# PokerKidtestBoard.net
KiCad netlist of a schematic drawn in Altium Designer
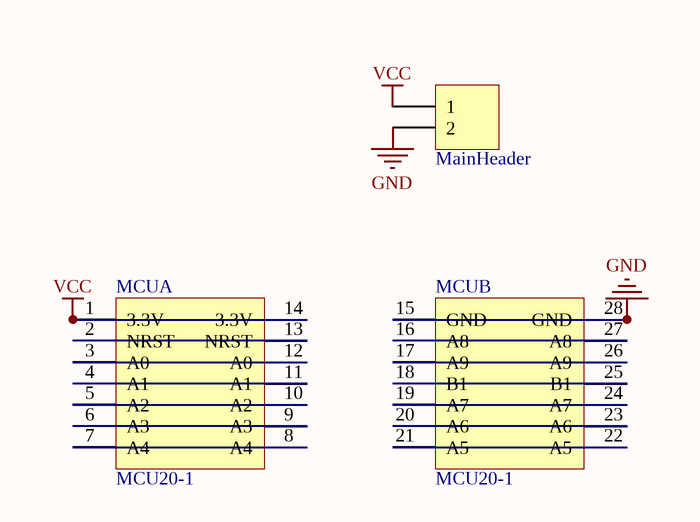
[diagram p0: PokerKidtestBoard.SchDoc]

(export (version "E")
  (design (tool "Eeschema 10.0.6"))
  (components
    (comp (ref "MainHeader")
      (value "691312510002")
      (footprint "691312510002")
      (description "WR-TBL Terminal Blocks Serie 312 – 5.08 mm")
      (fields
        (field (name "MANUFACTURER") "Würth Elektronik eiSos GmbH")
        (field (name "CREATED BY") "Karrer Zheng")
      )
      (libsource (lib "WE_WR-TBL_Pluggable System_5.08 mm_rev15basdasd") (part "691312510002"))
    )
    (comp (ref "MCU") (value "MCU20-1") (footprint "MCU20-1") (libsource (lib "Aryalib") (part "MCU20-1")))
  )
  (nets
    (net (code "1") (name "GND") (class "Default")
      (node (ref "MCU") (pin "15") (pinfunction "GND_15") (pintype "passive"))
      (node (ref "MCU") (pin "28") (pinfunction "GND_28") (pintype "passive"))
      (node (ref "MainHeader") (pin "2") (pinfunction "2_2") (pintype "passive"))
    )
    (net (code "2") (name "Net-(MCUA-A0-Pad12)") (class "Default")
      (node (ref "MCU") (pin "12") (pinfunction "A0_12") (pintype "passive"))
      (node (ref "MCU") (pin "3") (pinfunction "A0_3") (pintype "passive"))
    )
    (net (code "3") (name "Net-(MCUA-A1-Pad11)") (class "Default")
      (node (ref "MCU") (pin "11") (pinfunction "A1_11") (pintype "passive"))
      (node (ref "MCU") (pin "4") (pinfunction "A1_4") (pintype "passive"))
    )
    (net (code "4") (name "Net-(MCUA-A2-Pad10)") (class "Default")
      (node (ref "MCU") (pin "10") (pinfunction "A2_10") (pintype "passive"))
      (node (ref "MCU") (pin "5") (pinfunction "A2_5") (pintype "passive"))
    )
    (net (code "5") (name "Net-(MCUA-A3-Pad6)") (class "Default")
      (node (ref "MCU") (pin "6") (pinfunction "A3_6") (pintype "passive"))
      (node (ref "MCU") (pin "9") (pinfunction "A3_9") (pintype "passive"))
    )
    (net (code "6") (name "Net-(MCUA-A4-Pad7)") (class "Default")
      (node (ref "MCU") (pin "7") (pinfunction "A4_7") (pintype "passive"))
      (node (ref "MCU") (pin "8") (pinfunction "A4_8") (pintype "passive"))
    )
    (net (code "7") (name "Net-(MCUA-NRST-Pad13)") (class "Default")
      (node (ref "MCU") (pin "13") (pinfunction "NRST_13") (pintype "passive"))
      (node (ref "MCU") (pin "2") (pinfunction "NRST_2") (pintype "passive"))
    )
    (net (code "8") (name "Net-(MCUB-A5-Pad21)") (class "Default")
      (node (ref "MCU") (pin "21") (pinfunction "A5_21") (pintype "passive"))
      (node (ref "MCU") (pin "22") (pinfunction "A5_22") (pintype "passive"))
    )
    (net (code "9") (name "Net-(MCUB-A6-Pad20)") (class "Default")
      (node (ref "MCU") (pin "20") (pinfunction "A6_20") (pintype "passive"))
      (node (ref "MCU") (pin "23") (pinfunction "A6_23") (pintype "passive"))
    )
    (net (code "10") (name "Net-(MCUB-A7-Pad19)") (class "Default")
      (node (ref "MCU") (pin "19") (pinfunction "A7_19") (pintype "passive"))
      (node (ref "MCU") (pin "24") (pinfunction "A7_24") (pintype "passive"))
    )
    (net (code "11") (name "Net-(MCUB-A8-Pad16)") (class "Default")
      (node (ref "MCU") (pin "16") (pinfunction "A8_16") (pintype "passive"))
      (node (ref "MCU") (pin "27") (pinfunction "A8_27") (pintype "passive"))
    )
    (net (code "12") (name "Net-(MCUB-A9-Pad17)") (class "Default")
      (node (ref "MCU") (pin "17") (pinfunction "A9_17") (pintype "passive"))
      (node (ref "MCU") (pin "26") (pinfunction "A9_26") (pintype "passive"))
    )
    (net (code "13") (name "Net-(MCUB-B1-Pad18)") (class "Default")
      (node (ref "MCU") (pin "18") (pinfunction "B1_18") (pintype "passive"))
      (node (ref "MCU") (pin "25") (pinfunction "B1_25") (pintype "passive"))
    )
    (net (code "14") (name "VCC") (class "Default")
      (node (ref "MCU") (pin "1") (pinfunction "3.3V_1") (pintype "passive"))
      (node (ref "MCU") (pin "14") (pinfunction "3.3V_14") (pintype "passive"))
      (node (ref "MainHeader") (pin "1") (pinfunction "1_1") (pintype "passive"))
    )
  )
)
